# Circuit.net
KiCad netlist of a schematic drawn in EAGLE
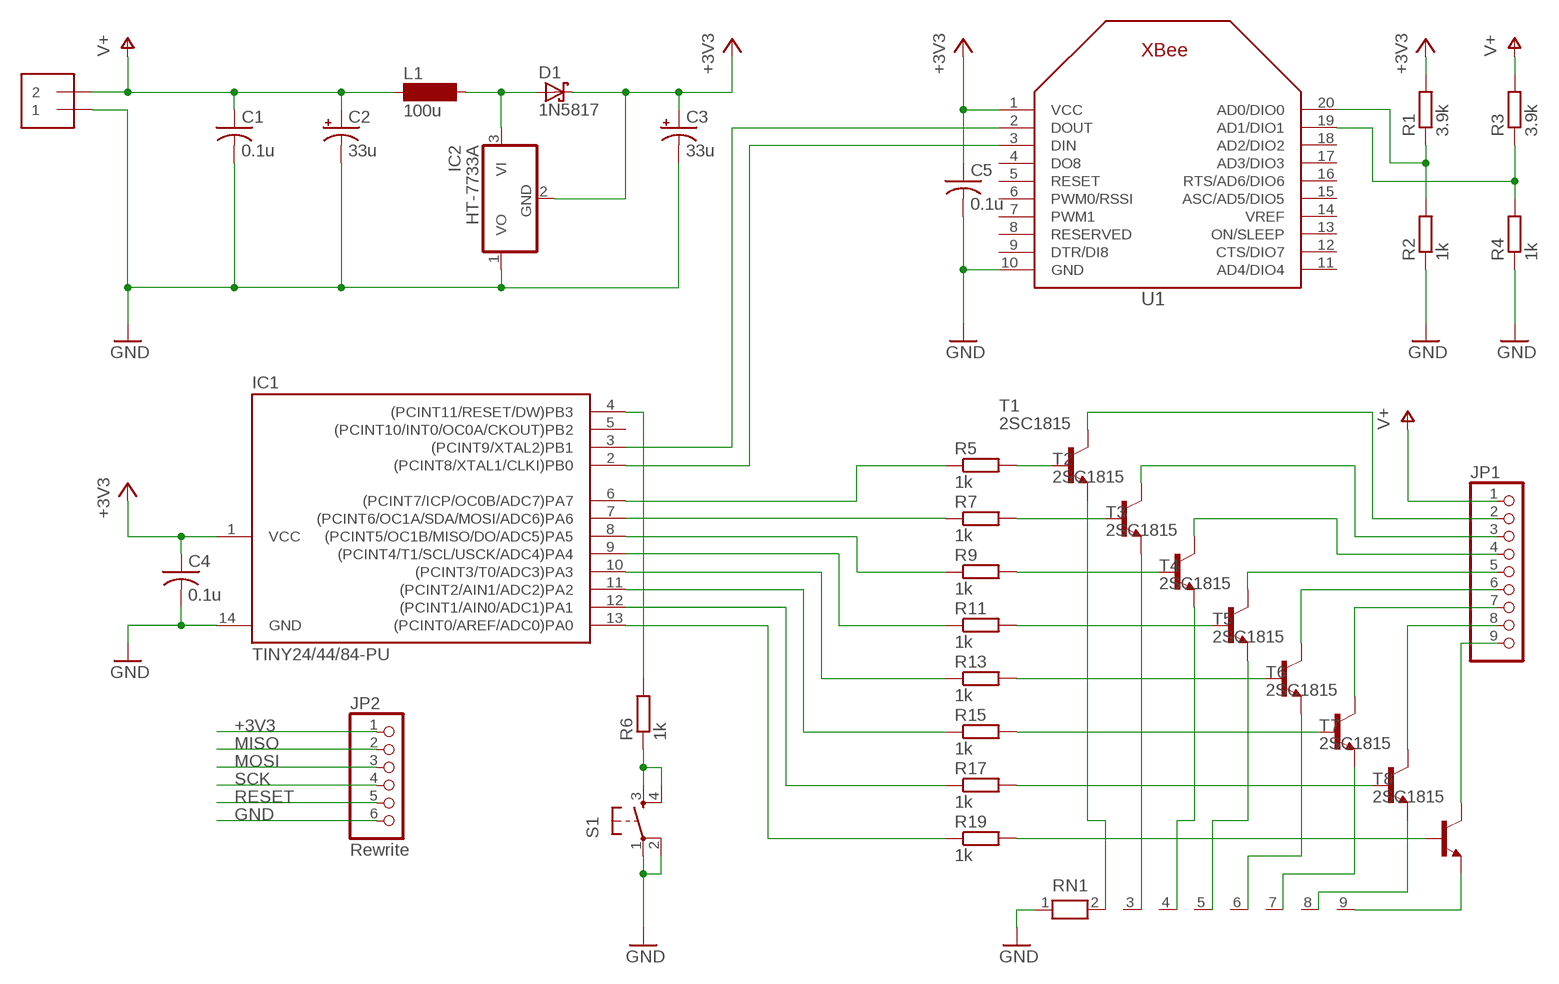
[diagram p0: schematic, sheet 1]

(export (version "E")
  (design (tool "Eeschema 10.0.6"))
  (components
    (comp (ref "C1")
      (value "0.1u")
      (footprint "eagle-import:C050-025X075")
      (libsource (lib "eagle-import") (part "C-US050-025X075"))
    )
    (comp (ref "C2")
      (value "33u")
      (footprint "eagle-import:E2,5-6")
      (libsource (lib "eagle-import") (part "CPOL-USE2.5-6"))
    )
    (comp (ref "C3")
      (value "33u")
      (footprint "eagle-import:E2,5-6")
      (libsource (lib "eagle-import") (part "CPOL-USE2.5-6"))
    )
    (comp (ref "C4")
      (value "0.1u")
      (footprint "eagle-import:C050-025X075")
      (libsource (lib "eagle-import") (part "C-US050-025X075"))
    )
    (comp (ref "C5")
      (value "0.1u")
      (footprint "eagle-import:C050-025X075")
      (libsource (lib "eagle-import") (part "C-US050-025X075"))
    )
    (comp (ref "D1")
      (value "1N5817")
      (footprint "eagle-import:DO41-7")
      (libsource (lib "eagle-import") (part "SCHOTTKY-DIODEDO41-7"))
    )
    (comp (ref "IC1")
      (value "TINY24/44/84-PU")
      (footprint "eagle-import:DIL14")
      (libsource (lib "eagle-import") (part "TINY24/44/84-PU"))
    )
    (comp (ref "IC2")
      (value "HT-7733A")
      (footprint "eagle-import:TO92")
      (libsource (lib "eagle-import") (part "78ZL05"))
    )
    (comp (ref "J1")
      (value "1X2-3.5MM")
      (footprint "eagle-import:1X2-3.5MM")
      (libsource (lib "eagle-import") (part "1X2-3.5MM"))
    )
    (comp (ref "JP1")
      (value "PINHD-1X9")
      (footprint "eagle-import:1X09-BIG")
      (libsource (lib "eagle-import") (part "PINHD-1X9"))
    )
    (comp (ref "JP2")
      (value "Rewrite")
      (footprint "eagle-import:1X06")
      (libsource (lib "eagle-import") (part "PINHD-1X6"))
    )
    (comp (ref "L1")
      (value "100u")
      (footprint "eagle-import:BS11")
      (libsource (lib "eagle-import") (part "BS11"))
    )
    (comp (ref "R1")
      (value "3.9k")
      (footprint "eagle-import:0204_7")
      (libsource (lib "eagle-import") (part "R-EU_0204/7"))
    )
    (comp (ref "R2")
      (value "1k")
      (footprint "eagle-import:0204_7")
      (libsource (lib "eagle-import") (part "R-EU_0204/7"))
    )
    (comp (ref "R3")
      (value "3.9k")
      (footprint "eagle-import:0204_7")
      (libsource (lib "eagle-import") (part "R-EU_0204/7"))
    )
    (comp (ref "R4")
      (value "1k")
      (footprint "eagle-import:0204_7")
      (libsource (lib "eagle-import") (part "R-EU_0204/7"))
    )
    (comp (ref "R5")
      (value "1k")
      (footprint "eagle-import:0204_7")
      (libsource (lib "eagle-import") (part "R-EU_0204/7"))
    )
    (comp (ref "R6")
      (value "1k")
      (footprint "eagle-import:0204_7")
      (libsource (lib "eagle-import") (part "R-EU_0204/7"))
    )
    (comp (ref "R7")
      (value "1k")
      (footprint "eagle-import:0204_7")
      (libsource (lib "eagle-import") (part "R-EU_0204/7"))
    )
    (comp (ref "R9")
      (value "1k")
      (footprint "eagle-import:0204_7")
      (libsource (lib "eagle-import") (part "R-EU_0204/7"))
    )
    (comp (ref "R11")
      (value "1k")
      (footprint "eagle-import:0204_7")
      (libsource (lib "eagle-import") (part "R-EU_0204/7"))
    )
    (comp (ref "R13")
      (value "1k")
      (footprint "eagle-import:0204_7")
      (libsource (lib "eagle-import") (part "R-EU_0204/7"))
    )
    (comp (ref "R15")
      (value "1k")
      (footprint "eagle-import:0204_7")
      (libsource (lib "eagle-import") (part "R-EU_0204/7"))
    )
    (comp (ref "R17")
      (value "1k")
      (footprint "eagle-import:0204_7")
      (libsource (lib "eagle-import") (part "R-EU_0204/7"))
    )
    (comp (ref "R19")
      (value "1k")
      (footprint "eagle-import:0204_7")
      (libsource (lib "eagle-import") (part "R-EU_0204/7"))
    )
    (comp (ref "RN1")
      (value "RN08")
      (footprint "eagle-import:RN-9")
      (libsource (lib "eagle-import") (part "RN08"))
    )
    (comp (ref "S1")
      (value "TAC_SWITCHPTH")
      (footprint "eagle-import:TACTILE-PTH")
      (libsource (lib "eagle-import") (part "TAC_SWITCHPTH"))
    )
    (comp (ref "T1")
      (value "2SC1815")
      (footprint "eagle-import:TO92-ECB")
      (libsource (lib "eagle-import") (part "2SC1815"))
    )
    (comp (ref "T2")
      (value "2SC1815")
      (footprint "eagle-import:TO92-ECB")
      (libsource (lib "eagle-import") (part "2SC1815"))
    )
    (comp (ref "T3")
      (value "2SC1815")
      (footprint "eagle-import:TO92-ECB")
      (libsource (lib "eagle-import") (part "2SC1815"))
    )
    (comp (ref "T4")
      (value "2SC1815")
      (footprint "eagle-import:TO92-ECB")
      (libsource (lib "eagle-import") (part "2SC1815"))
    )
    (comp (ref "T5")
      (value "2SC1815")
      (footprint "eagle-import:TO92-ECB")
      (libsource (lib "eagle-import") (part "2SC1815"))
    )
    (comp (ref "T6")
      (value "2SC1815")
      (footprint "eagle-import:TO92-ECB")
      (libsource (lib "eagle-import") (part "2SC1815"))
    )
    (comp (ref "T7")
      (value "2SC1815")
      (footprint "eagle-import:TO92-ECB")
      (libsource (lib "eagle-import") (part "2SC1815"))
    )
    (comp (ref "T8")
      (value "2SC1815")
      (footprint "eagle-import:TO92-ECB")
      (libsource (lib "eagle-import") (part "2SC1815"))
    )
    (comp (ref "U1")
      (value "XBEE")
      (footprint "eagle-import:XBEE")
      (libsource (lib "eagle-import") (part "XBEE"))
    )
  )
  (nets
    (net (code "1") (name "+3V3") (class "Default")
      (node (ref "C3") (pin "+") (pinfunction "+_+") (pintype "passive"))
      (node (ref "C4") (pin "1") (pinfunction "1_1") (pintype "passive"))
      (node (ref "C5") (pin "1") (pinfunction "1_1") (pintype "passive"))
      (node (ref "D1") (pin "C") (pinfunction "C_C") (pintype "passive"))
      (node (ref "IC1") (pin "1") (pinfunction "VCC_1") (pintype "power_in"))
      (node (ref "IC2") (pin "2") (pinfunction "GND_2") (pintype "passive"))
      (node (ref "JP2") (pin "1") (pinfunction "1_1") (pintype "passive"))
      (node (ref "R1") (pin "2") (pinfunction "2_2") (pintype "passive"))
      (node (ref "U1") (pin "1") (pinfunction "VCC_1") (pintype "power_in"))
    )
    (net (code "2") (name "/MISO") (class "Default")
      (node (ref "IC1") (pin "8") (pinfunction "(PCINT5/OC1B/MISO/DO/ADC5)PA5_8") (pintype "bidirectional"))
      (node (ref "JP2") (pin "2") (pinfunction "2_2") (pintype "passive"))
      (node (ref "R9") (pin "1") (pinfunction "1_1") (pintype "passive"))
    )
    (net (code "3") (name "/MOSI") (class "Default")
      (node (ref "IC1") (pin "7") (pinfunction "(PCINT6/OC1A/SDA/MOSI/ADC6)PA6_7") (pintype "bidirectional"))
      (node (ref "JP2") (pin "3") (pinfunction "3_3") (pintype "passive"))
      (node (ref "R7") (pin "1") (pinfunction "1_1") (pintype "passive"))
    )
    (net (code "4") (name "/RESET") (class "Default")
      (node (ref "IC1") (pin "4") (pinfunction "(PCINT11/RESET/DW)PB3_4") (pintype "bidirectional"))
      (node (ref "JP2") (pin "5") (pinfunction "5_5") (pintype "passive"))
      (node (ref "R6") (pin "2") (pinfunction "2_2") (pintype "passive"))
    )
    (net (code "5") (name "/SCK") (class "Default")
      (node (ref "IC1") (pin "9") (pinfunction "(PCINT4/T1/SCL/USCK/ADC4)PA4_9") (pintype "bidirectional"))
      (node (ref "JP2") (pin "4") (pinfunction "4_4") (pintype "passive"))
      (node (ref "R11") (pin "1") (pinfunction "1_1") (pintype "passive"))
    )
    (net (code "6") (name "GND") (class "Default")
      (node (ref "C1") (pin "2") (pinfunction "2_2") (pintype "passive"))
      (node (ref "C2") (pin "-") (pinfunction "-_-") (pintype "passive"))
      (node (ref "C3") (pin "-") (pinfunction "-_-") (pintype "passive"))
      (node (ref "C4") (pin "2") (pinfunction "2_2") (pintype "passive"))
      (node (ref "C5") (pin "2") (pinfunction "2_2") (pintype "passive"))
      (node (ref "IC1") (pin "14") (pinfunction "GND_14") (pintype "power_in"))
      (node (ref "IC2") (pin "1") (pinfunction "VO_1") (pintype "passive"))
      (node (ref "J1") (pin "1") (pinfunction "1_1") (pintype "passive"))
      (node (ref "JP2") (pin "6") (pinfunction "6_6") (pintype "passive"))
      (node (ref "R2") (pin "1") (pinfunction "1_1") (pintype "passive"))
      (node (ref "R4") (pin "1") (pinfunction "1_1") (pintype "passive"))
      (node (ref "RN1") (pin "1") (pinfunction "1_1") (pintype "passive"))
      (node (ref "S1") (pin "1") (pinfunction "1_1") (pintype "passive"))
      (node (ref "S1") (pin "2") (pinfunction "2_2") (pintype "passive"))
      (node (ref "U1") (pin "10") (pinfunction "GND_10") (pintype "power_in"))
    )
    (net (code "7") (name "Net-(IC1-(PCINT0{slash}AREF{slash}ADC0)PA0)") (class "Default")
      (node (ref "IC1") (pin "13") (pinfunction "(PCINT0/AREF/ADC0)PA0_13") (pintype "bidirectional"))
      (node (ref "R19") (pin "1") (pinfunction "1_1") (pintype "passive"))
    )
    (net (code "8") (name "Net-(IC1-(PCINT1{slash}AIN0{slash}ADC1)PA1)") (class "Default")
      (node (ref "IC1") (pin "12") (pinfunction "(PCINT1/AIN0/ADC1)PA1_12") (pintype "bidirectional"))
      (node (ref "R17") (pin "1") (pinfunction "1_1") (pintype "passive"))
    )
    (net (code "9") (name "Net-(IC1-(PCINT2{slash}AIN1{slash}ADC2)PA2)") (class "Default")
      (node (ref "IC1") (pin "11") (pinfunction "(PCINT2/AIN1/ADC2)PA2_11") (pintype "bidirectional"))
      (node (ref "R15") (pin "1") (pinfunction "1_1") (pintype "passive"))
    )
    (net (code "10") (name "Net-(IC1-(PCINT3{slash}T0{slash}ADC3)PA3)") (class "Default")
      (node (ref "IC1") (pin "10") (pinfunction "(PCINT3/T0/ADC3)PA3_10") (pintype "bidirectional"))
      (node (ref "R13") (pin "1") (pinfunction "1_1") (pintype "passive"))
    )
    (net (code "11") (name "Net-(IC1-(PCINT7{slash}ICP{slash}OC0B{slash}ADC7)PA7)") (class "Default")
      (node (ref "IC1") (pin "6") (pinfunction "(PCINT7/ICP/OC0B/ADC7)PA7_6") (pintype "bidirectional"))
      (node (ref "R5") (pin "1") (pinfunction "1_1") (pintype "passive"))
    )
    (net (code "12") (name "Net-(IC1-(PCINT8{slash}XTAL1{slash}CLKI)PB0)") (class "Default")
      (node (ref "IC1") (pin "2") (pinfunction "(PCINT8/XTAL1/CLKI)PB0_2") (pintype "bidirectional"))
      (node (ref "U1") (pin "3") (pinfunction "DIN_3") (pintype "input"))
    )
    (net (code "13") (name "Net-(IC1-(PCINT9{slash}XTAL2)PB1)") (class "Default")
      (node (ref "IC1") (pin "3") (pinfunction "(PCINT9/XTAL2)PB1_3") (pintype "bidirectional"))
      (node (ref "U1") (pin "2") (pinfunction "DOUT_2") (pintype "output"))
    )
    (net (code "14") (name "Net-(IC2-VI)") (class "Default")
      (node (ref "D1") (pin "A") (pinfunction "A_A") (pintype "passive"))
      (node (ref "IC2") (pin "3") (pinfunction "VI_3") (pintype "input"))
      (node (ref "L1") (pin "2") (pinfunction "2_2") (pintype "passive"))
    )
    (net (code "15") (name "Net-(JP1-Pad2)") (class "Default")
      (node (ref "JP1") (pin "2") (pinfunction "2_2") (pintype "passive"))
      (node (ref "T1") (pin "C") (pinfunction "C_C") (pintype "passive"))
    )
    (net (code "16") (name "Net-(JP1-Pad3)") (class "Default")
      (node (ref "JP1") (pin "3") (pinfunction "3_3") (pintype "passive"))
      (node (ref "T2") (pin "C") (pinfunction "C_C") (pintype "passive"))
    )
    (net (code "17") (name "Net-(JP1-Pad4)") (class "Default")
      (node (ref "JP1") (pin "4") (pinfunction "4_4") (pintype "passive"))
      (node (ref "T3") (pin "C") (pinfunction "C_C") (pintype "passive"))
    )
    (net (code "18") (name "Net-(JP1-Pad5)") (class "Default")
      (node (ref "JP1") (pin "5") (pinfunction "5_5") (pintype "passive"))
      (node (ref "T4") (pin "C") (pinfunction "C_C") (pintype "passive"))
    )
    (net (code "19") (name "Net-(JP1-Pad6)") (class "Default")
      (node (ref "JP1") (pin "6") (pinfunction "6_6") (pintype "passive"))
      (node (ref "T5") (pin "C") (pinfunction "C_C") (pintype "passive"))
    )
    (net (code "20") (name "Net-(JP1-Pad7)") (class "Default")
      (node (ref "JP1") (pin "7") (pinfunction "7_7") (pintype "passive"))
      (node (ref "T6") (pin "C") (pinfunction "C_C") (pintype "passive"))
    )
    (net (code "21") (name "Net-(JP1-Pad8)") (class "Default")
      (node (ref "JP1") (pin "8") (pinfunction "8_8") (pintype "passive"))
      (node (ref "T7") (pin "C") (pinfunction "C_C") (pintype "passive"))
    )
    (net (code "22") (name "Net-(JP1-Pad9)") (class "Default")
      (node (ref "JP1") (pin "9") (pinfunction "9_9") (pintype "passive"))
      (node (ref "T8") (pin "C") (pinfunction "C_C") (pintype "passive"))
    )
    (net (code "23") (name "Net-(R5-Pad2)") (class "Default")
      (node (ref "R5") (pin "2") (pinfunction "2_2") (pintype "passive"))
      (node (ref "T1") (pin "B") (pinfunction "B_B") (pintype "passive"))
    )
    (net (code "24") (name "Net-(R6-Pad1)") (class "Default")
      (node (ref "R6") (pin "1") (pinfunction "1_1") (pintype "passive"))
      (node (ref "S1") (pin "3") (pinfunction "3_3") (pintype "passive"))
      (node (ref "S1") (pin "4") (pinfunction "4_4") (pintype "passive"))
    )
    (net (code "25") (name "Net-(R7-Pad2)") (class "Default")
      (node (ref "R7") (pin "2") (pinfunction "2_2") (pintype "passive"))
      (node (ref "T2") (pin "B") (pinfunction "B_B") (pintype "passive"))
    )
    (net (code "26") (name "Net-(R9-Pad2)") (class "Default")
      (node (ref "R9") (pin "2") (pinfunction "2_2") (pintype "passive"))
      (node (ref "T3") (pin "B") (pinfunction "B_B") (pintype "passive"))
    )
    (net (code "27") (name "Net-(R11-Pad2)") (class "Default")
      (node (ref "R11") (pin "2") (pinfunction "2_2") (pintype "passive"))
      (node (ref "T4") (pin "B") (pinfunction "B_B") (pintype "passive"))
    )
    (net (code "28") (name "Net-(R13-Pad2)") (class "Default")
      (node (ref "R13") (pin "2") (pinfunction "2_2") (pintype "passive"))
      (node (ref "T5") (pin "B") (pinfunction "B_B") (pintype "passive"))
    )
    (net (code "29") (name "Net-(R15-Pad2)") (class "Default")
      (node (ref "R15") (pin "2") (pinfunction "2_2") (pintype "passive"))
      (node (ref "T6") (pin "B") (pinfunction "B_B") (pintype "passive"))
    )
    (net (code "30") (name "Net-(R17-Pad2)") (class "Default")
      (node (ref "R17") (pin "2") (pinfunction "2_2") (pintype "passive"))
      (node (ref "T7") (pin "B") (pinfunction "B_B") (pintype "passive"))
    )
    (net (code "31") (name "Net-(R19-Pad2)") (class "Default")
      (node (ref "R19") (pin "2") (pinfunction "2_2") (pintype "passive"))
      (node (ref "T8") (pin "B") (pinfunction "B_B") (pintype "passive"))
    )
    (net (code "32") (name "Net-(RN1-Pad2)") (class "Default")
      (node (ref "RN1") (pin "2") (pinfunction "2_2") (pintype "passive"))
      (node (ref "T1") (pin "E") (pinfunction "E_E") (pintype "passive"))
    )
    (net (code "33") (name "Net-(RN1-Pad3)") (class "Default")
      (node (ref "RN1") (pin "3") (pinfunction "3_3") (pintype "passive"))
      (node (ref "T2") (pin "E") (pinfunction "E_E") (pintype "passive"))
    )
    (net (code "34") (name "Net-(RN1-Pad4)") (class "Default")
      (node (ref "RN1") (pin "4") (pinfunction "4_4") (pintype "passive"))
      (node (ref "T3") (pin "E") (pinfunction "E_E") (pintype "passive"))
    )
    (net (code "35") (name "Net-(RN1-Pad5)") (class "Default")
      (node (ref "RN1") (pin "5") (pinfunction "5_5") (pintype "passive"))
      (node (ref "T4") (pin "E") (pinfunction "E_E") (pintype "passive"))
    )
    (net (code "36") (name "Net-(RN1-Pad6)") (class "Default")
      (node (ref "RN1") (pin "6") (pinfunction "6_6") (pintype "passive"))
      (node (ref "T5") (pin "E") (pinfunction "E_E") (pintype "passive"))
    )
    (net (code "37") (name "Net-(RN1-Pad7)") (class "Default")
      (node (ref "RN1") (pin "7") (pinfunction "7_7") (pintype "passive"))
      (node (ref "T6") (pin "E") (pinfunction "E_E") (pintype "passive"))
    )
    (net (code "38") (name "Net-(RN1-Pad8)") (class "Default")
      (node (ref "RN1") (pin "8") (pinfunction "8_8") (pintype "passive"))
      (node (ref "T7") (pin "E") (pinfunction "E_E") (pintype "passive"))
    )
    (net (code "39") (name "Net-(RN1-Pad9)") (class "Default")
      (node (ref "RN1") (pin "9") (pinfunction "9_9") (pintype "passive"))
      (node (ref "T8") (pin "E") (pinfunction "E_E") (pintype "passive"))
    )
    (net (code "40") (name "Net-(U1-AD0{slash}DIO0)") (class "Default")
      (node (ref "R1") (pin "1") (pinfunction "1_1") (pintype "passive"))
      (node (ref "R2") (pin "2") (pinfunction "2_2") (pintype "passive"))
      (node (ref "U1") (pin "20") (pinfunction "AD0/DIO0_20") (pintype "bidirectional"))
    )
    (net (code "41") (name "Net-(U1-AD1{slash}DIO1)") (class "Default")
      (node (ref "R3") (pin "1") (pinfunction "1_1") (pintype "passive"))
      (node (ref "R4") (pin "2") (pinfunction "2_2") (pintype "passive"))
      (node (ref "U1") (pin "19") (pinfunction "AD1/DIO1_19") (pintype "bidirectional"))
    )
    (net (code "42") (name "V+") (class "Default")
      (node (ref "C1") (pin "1") (pinfunction "1_1") (pintype "passive"))
      (node (ref "C2") (pin "+") (pinfunction "+_+") (pintype "passive"))
      (node (ref "J1") (pin "2") (pinfunction "2_2") (pintype "passive"))
      (node (ref "JP1") (pin "1") (pinfunction "1_1") (pintype "passive"))
      (node (ref "L1") (pin "1") (pinfunction "1_1") (pintype "passive"))
      (node (ref "R3") (pin "2") (pinfunction "2_2") (pintype "passive"))
    )
    (net (code "43") (name "unconnected-(IC1-(PCINT10{slash}INT0{slash}OC0A{slash}CKOUT)PB2-Pad5)") (class "Default")
      (node (ref "IC1") (pin "5") (pinfunction "(PCINT10/INT0/OC0A/CKOUT)PB2_5") (pintype "bidirectional"))
    )
    (net (code "44") (name "unconnected-(U1-AD2{slash}DIO2-Pad18)") (class "Default")
      (node (ref "U1") (pin "18") (pinfunction "AD2/DIO2_18") (pintype "bidirectional"))
    )
    (net (code "45") (name "unconnected-(U1-AD3{slash}DIO3-Pad17)") (class "Default")
      (node (ref "U1") (pin "17") (pinfunction "AD3/DIO3_17") (pintype "bidirectional"))
    )
    (net (code "46") (name "unconnected-(U1-AD4{slash}DIO4-Pad11)") (class "Default")
      (node (ref "U1") (pin "11") (pinfunction "AD4/DIO4_11") (pintype "bidirectional"))
    )
    (net (code "47") (name "unconnected-(U1-ASC{slash}AD5{slash}DIO5-Pad15)") (class "Default")
      (node (ref "U1") (pin "15") (pinfunction "ASC/AD5/DIO5_15") (pintype "bidirectional"))
    )
    (net (code "48") (name "unconnected-(U1-CTS{slash}DIO7-Pad12)") (class "Default")
      (node (ref "U1") (pin "12") (pinfunction "CTS/DIO7_12") (pintype "bidirectional"))
    )
    (net (code "49") (name "unconnected-(U1-DO8-Pad4)") (class "Default")
      (node (ref "U1") (pin "4") (pinfunction "DO8_4") (pintype "output"))
    )
    (net (code "50") (name "unconnected-(U1-DTR{slash}DI8-Pad9)") (class "Default")
      (node (ref "U1") (pin "9") (pinfunction "DTR/DI8_9") (pintype "input"))
    )
    (net (code "51") (name "unconnected-(U1-ON{slash}SLEEP-Pad13)") (class "Default")
      (node (ref "U1") (pin "13") (pinfunction "ON/SLEEP_13") (pintype "output"))
    )
    (net (code "52") (name "unconnected-(U1-PWM0{slash}RSSI-Pad6)") (class "Default")
      (node (ref "U1") (pin "6") (pinfunction "PWM0/RSSI_6") (pintype "output"))
    )
    (net (code "53") (name "unconnected-(U1-PWM1-Pad7)") (class "Default")
      (node (ref "U1") (pin "7") (pinfunction "PWM1_7") (pintype "output"))
    )
    (net (code "54") (name "unconnected-(U1-RESERVED-Pad8)") (class "Default")
      (node (ref "U1") (pin "8") (pinfunction "RESERVED_8") (pintype "no_connect"))
    )
    (net (code "55") (name "unconnected-(U1-RESET-Pad5)") (class "Default")
      (node (ref "U1") (pin "5") (pinfunction "RESET_5") (pintype "input"))
    )
    (net (code "56") (name "unconnected-(U1-RTS{slash}AD6{slash}DIO6-Pad16)") (class "Default")
      (node (ref "U1") (pin "16") (pinfunction "RTS/AD6/DIO6_16") (pintype "bidirectional"))
    )
    (net (code "57") (name "unconnected-(U1-VREF-Pad14)") (class "Default")
      (node (ref "U1") (pin "14") (pinfunction "VREF_14") (pintype "input"))
    )
  )
)
